# gvs1.net
KiCad netlist of a schematic drawn in EAGLE
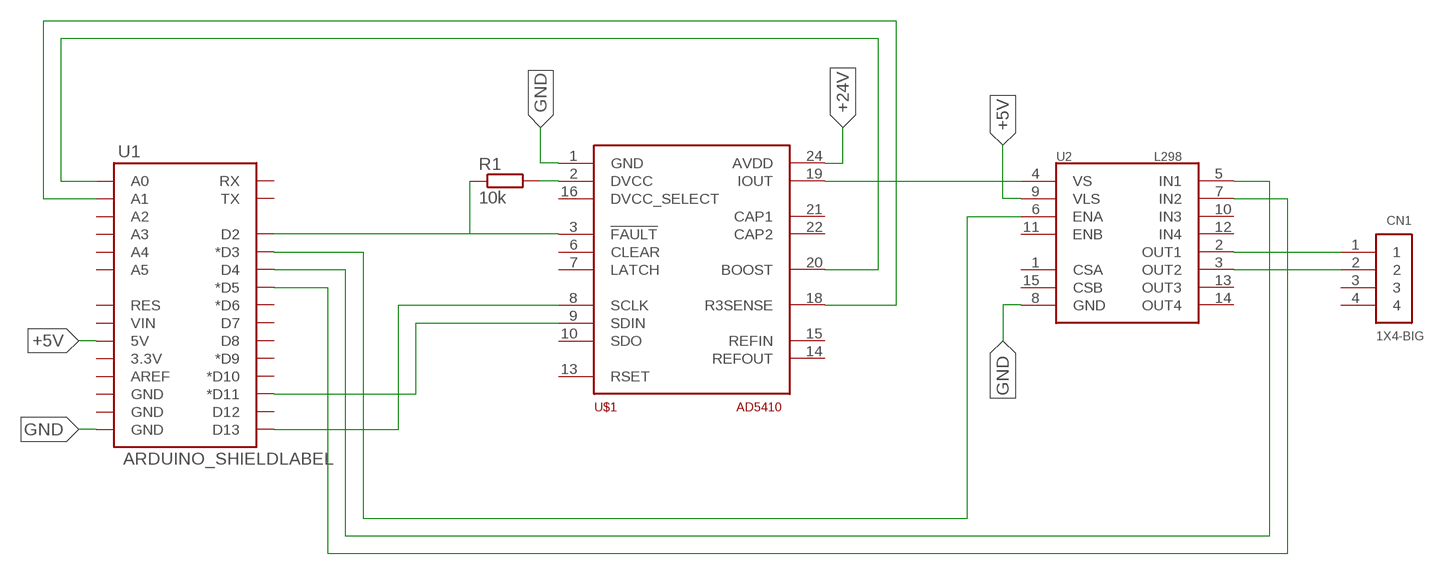
[diagram p0: schematic, sheet 1]

(export (version "E")
  (design (tool "Eeschema 10.0.6"))
  (components
    (comp (ref "CN1")
      (value "1X4-BIG")
      (footprint "eagle-import:1X04-BIG")
      (libsource (lib "eagle-import") (part "1X4-BIG"))
    )
    (comp (ref "R1")
      (value "10k")
      (footprint "eagle-import:0204V")
      (libsource (lib "eagle-import") (part "R-EU_0204/2V"))
    )
    (comp (ref "U$1")
      (value "AD5410")
      (footprint "eagle-import:TSSOP24")
      (libsource (lib "eagle-import") (part "AD5410"))
    )
    (comp (ref "U1")
      (value "ARDUINO_SHIELDLABEL")
      (footprint "eagle-import:DUEMILANOVE_SHIELD")
      (libsource (lib "eagle-import") (part "ARDUINO_SHIELDLABEL"))
    )
    (comp (ref "U2")
      (value "L298")
      (footprint "eagle-import:MULTIWATT15")
      (libsource (lib "eagle-import") (part "L298"))
    )
  )
  (nets
    (net (code "1") (name "+5V") (class "Default")
      (node (ref "U1") (pin "5V") (pinfunction "5V_5V") (pintype "bidirectional"))
      (node (ref "U2") (pin "9") (pinfunction "VLS_9") (pintype "bidirectional"))
    )
    (net (code "2") (name "+24V") (class "Default")
      (node (ref "U$1") (pin "24") (pinfunction "AVDD_24") (pintype "bidirectional"))
    )
    (net (code "3") (name "GND") (class "Default")
      (node (ref "U$1") (pin "1") (pinfunction "GND_1") (pintype "bidirectional"))
      (node (ref "U1") (pin "GND@0") (pinfunction "GND_GND@0") (pintype "bidirectional"))
      (node (ref "U2") (pin "8") (pinfunction "GND_8") (pintype "bidirectional"))
    )
    (net (code "4") (name "Net-(U$1-BOOST)") (class "Default")
      (node (ref "U$1") (pin "20") (pinfunction "BOOST_20") (pintype "bidirectional"))
      (node (ref "U1") (pin "A0") (pinfunction "A0_A0") (pintype "bidirectional"))
    )
    (net (code "5") (name "Net-(U$1-DVCC)") (class "Default")
      (node (ref "R1") (pin "2") (pinfunction "2_2") (pintype "passive"))
      (node (ref "U$1") (pin "2") (pinfunction "DVCC_2") (pintype "bidirectional"))
    )
    (net (code "6") (name "Net-(U$1-IOUT)") (class "Default")
      (node (ref "U$1") (pin "19") (pinfunction "IOUT_19") (pintype "bidirectional"))
      (node (ref "U2") (pin "4") (pinfunction "VS_4") (pintype "bidirectional"))
    )
    (net (code "7") (name "Net-(U$1-R3SENSE)") (class "Default")
      (node (ref "U$1") (pin "18") (pinfunction "R3SENSE_18") (pintype "bidirectional"))
      (node (ref "U1") (pin "A1") (pinfunction "A1_A1") (pintype "bidirectional"))
    )
    (net (code "8") (name "Net-(U$1-SCLK)") (class "Default")
      (node (ref "U$1") (pin "8") (pinfunction "SCLK_8") (pintype "bidirectional"))
      (node (ref "U1") (pin "D13") (pinfunction "D13_D13") (pintype "bidirectional"))
    )
    (net (code "9") (name "Net-(U$1-SDIN)") (class "Default")
      (node (ref "U$1") (pin "9") (pinfunction "SDIN_9") (pintype "bidirectional"))
      (node (ref "U1") (pin "D11") (pinfunction "*D11_D11") (pintype "bidirectional"))
    )
    (net (code "10") (name "Net-(U$1-~{FAULT})") (class "Default")
      (node (ref "R1") (pin "1") (pinfunction "1_1") (pintype "passive"))
      (node (ref "U$1") (pin "3") (pinfunction "~{FAULT}_3") (pintype "bidirectional"))
      (node (ref "U1") (pin "D2") (pinfunction "D2_D2") (pintype "bidirectional"))
    )
    (net (code "11") (name "Net-(U1-*D3)") (class "Default")
      (node (ref "U1") (pin "D3") (pinfunction "*D3_D3") (pintype "bidirectional"))
      (node (ref "U2") (pin "6") (pinfunction "ENA_6") (pintype "bidirectional"))
    )
    (net (code "12") (name "Net-(U1-*D5)") (class "Default")
      (node (ref "U1") (pin "D5") (pinfunction "*D5_D5") (pintype "bidirectional"))
      (node (ref "U2") (pin "7") (pinfunction "IN2_7") (pintype "bidirectional"))
    )
    (net (code "13") (name "Net-(U2-IN1)") (class "Default")
      (node (ref "U1") (pin "D4") (pinfunction "D4_D4") (pintype "bidirectional"))
      (node (ref "U2") (pin "5") (pinfunction "IN1_5") (pintype "bidirectional"))
    )
    (net (code "14") (name "Net-(U2-OUT1)") (class "Default")
      (node (ref "CN1") (pin "1") (pinfunction "1_1") (pintype "bidirectional"))
      (node (ref "U2") (pin "2") (pinfunction "OUT1_2") (pintype "bidirectional"))
    )
    (net (code "15") (name "Net-(U2-OUT2)") (class "Default")
      (node (ref "CN1") (pin "2") (pinfunction "2_2") (pintype "bidirectional"))
      (node (ref "U2") (pin "3") (pinfunction "OUT2_3") (pintype "bidirectional"))
    )
    (net (code "16") (name "unconnected-(CN1-Pad3)") (class "Default")
      (node (ref "CN1") (pin "3") (pinfunction "3_3") (pintype "bidirectional"))
    )
    (net (code "17") (name "unconnected-(CN1-Pad4)") (class "Default")
      (node (ref "CN1") (pin "4") (pinfunction "4_4") (pintype "bidirectional"))
    )
    (net (code "18") (name "unconnected-(U$1-CAP1-Pad21)") (class "Default")
      (node (ref "U$1") (pin "21") (pinfunction "CAP1_21") (pintype "bidirectional"))
    )
    (net (code "19") (name "unconnected-(U$1-CAP2-Pad22)") (class "Default")
      (node (ref "U$1") (pin "22") (pinfunction "CAP2_22") (pintype "bidirectional"))
    )
    (net (code "20") (name "unconnected-(U$1-CLEAR-Pad6)") (class "Default")
      (node (ref "U$1") (pin "6") (pinfunction "CLEAR_6") (pintype "bidirectional"))
    )
    (net (code "21") (name "unconnected-(U$1-DVCC_SELECT-Pad16)") (class "Default")
      (node (ref "U$1") (pin "16") (pinfunction "DVCC_SELECT_16") (pintype "bidirectional"))
    )
    (net (code "22") (name "unconnected-(U$1-LATCH-Pad7)") (class "Default")
      (node (ref "U$1") (pin "7") (pinfunction "LATCH_7") (pintype "bidirectional"))
    )
    (net (code "23") (name "unconnected-(U$1-REFIN-Pad15)") (class "Default")
      (node (ref "U$1") (pin "15") (pinfunction "REFIN_15") (pintype "bidirectional"))
    )
    (net (code "24") (name "unconnected-(U$1-REFOUT-Pad14)") (class "Default")
      (node (ref "U$1") (pin "14") (pinfunction "REFOUT_14") (pintype "bidirectional"))
    )
    (net (code "25") (name "unconnected-(U$1-RSET-Pad13)") (class "Default")
      (node (ref "U$1") (pin "13") (pinfunction "RSET_13") (pintype "bidirectional"))
    )
    (net (code "26") (name "unconnected-(U$1-SDO-Pad10)") (class "Default")
      (node (ref "U$1") (pin "10") (pinfunction "SDO_10") (pintype "bidirectional"))
    )
    (net (code "27") (name "unconnected-(U1-*D6-PadD6)") (class "Default")
      (node (ref "U1") (pin "D6") (pinfunction "*D6_D6") (pintype "bidirectional"))
    )
    (net (code "28") (name "unconnected-(U1-*D9-PadD9)") (class "Default")
      (node (ref "U1") (pin "D9") (pinfunction "*D9_D9") (pintype "bidirectional"))
    )
    (net (code "29") (name "unconnected-(U1-*D10-PadD10)") (class "Default")
      (node (ref "U1") (pin "D10") (pinfunction "*D10_D10") (pintype "bidirectional"))
    )
    (net (code "30") (name "unconnected-(U1-GND-PadGND@1)") (class "Default")
      (node (ref "U1") (pin "GND@1") (pinfunction "GND_GND@1") (pintype "bidirectional"))
    )
    (net (code "31") (name "unconnected-(U1-GND-PadGND@2)") (class "Default")
      (node (ref "U1") (pin "GND@2") (pinfunction "GND_GND@2") (pintype "bidirectional"))
    )
    (net (code "32") (name "unconnected-(U1-Pad3.3V)") (class "Default")
      (node (ref "U1") (pin "3.3V") (pinfunction "3.3V_3.3V") (pintype "bidirectional"))
    )
    (net (code "33") (name "unconnected-(U1-PadA2)") (class "Default")
      (node (ref "U1") (pin "A2") (pinfunction "A2_A2") (pintype "bidirectional"))
    )
    (net (code "34") (name "unconnected-(U1-PadA3)") (class "Default")
      (node (ref "U1") (pin "A3") (pinfunction "A3_A3") (pintype "bidirectional"))
    )
    (net (code "35") (name "unconnected-(U1-PadA4)") (class "Default")
      (node (ref "U1") (pin "A4") (pinfunction "A4_A4") (pintype "bidirectional"))
    )
    (net (code "36") (name "unconnected-(U1-PadA5)") (class "Default")
      (node (ref "U1") (pin "A5") (pinfunction "A5_A5") (pintype "bidirectional"))
    )
    (net (code "37") (name "unconnected-(U1-PadAREF)") (class "Default")
      (node (ref "U1") (pin "AREF") (pinfunction "AREF_AREF") (pintype "bidirectional"))
    )
    (net (code "38") (name "unconnected-(U1-PadD7)") (class "Default")
      (node (ref "U1") (pin "D7") (pinfunction "D7_D7") (pintype "bidirectional"))
    )
    (net (code "39") (name "unconnected-(U1-PadD8)") (class "Default")
      (node (ref "U1") (pin "D8") (pinfunction "D8_D8") (pintype "bidirectional"))
    )
    (net (code "40") (name "unconnected-(U1-PadD12)") (class "Default")
      (node (ref "U1") (pin "D12") (pinfunction "D12_D12") (pintype "bidirectional"))
    )
    (net (code "41") (name "unconnected-(U1-PadRES)") (class "Default")
      (node (ref "U1") (pin "RES") (pinfunction "RES_RES") (pintype "bidirectional"))
    )
    (net (code "42") (name "unconnected-(U1-PadRX)") (class "Default")
      (node (ref "U1") (pin "RX") (pinfunction "RX_RX") (pintype "bidirectional"))
    )
    (net (code "43") (name "unconnected-(U1-PadTX)") (class "Default")
      (node (ref "U1") (pin "TX") (pinfunction "TX_TX") (pintype "bidirectional"))
    )
    (net (code "44") (name "unconnected-(U1-PadVIN)") (class "Default")
      (node (ref "U1") (pin "VIN") (pinfunction "VIN_VIN") (pintype "bidirectional"))
    )
    (net (code "45") (name "unconnected-(U2-CSA-Pad1)") (class "Default")
      (node (ref "U2") (pin "1") (pinfunction "CSA_1") (pintype "bidirectional"))
    )
    (net (code "46") (name "unconnected-(U2-CSB-Pad15)") (class "Default")
      (node (ref "U2") (pin "15") (pinfunction "CSB_15") (pintype "bidirectional"))
    )
    (net (code "47") (name "unconnected-(U2-ENB-Pad11)") (class "Default")
      (node (ref "U2") (pin "11") (pinfunction "ENB_11") (pintype "bidirectional"))
    )
    (net (code "48") (name "unconnected-(U2-IN3-Pad10)") (class "Default")
      (node (ref "U2") (pin "10") (pinfunction "IN3_10") (pintype "bidirectional"))
    )
    (net (code "49") (name "unconnected-(U2-IN4-Pad12)") (class "Default")
      (node (ref "U2") (pin "12") (pinfunction "IN4_12") (pintype "bidirectional"))
    )
    (net (code "50") (name "unconnected-(U2-OUT3-Pad13)") (class "Default")
      (node (ref "U2") (pin "13") (pinfunction "OUT3_13") (pintype "bidirectional"))
    )
    (net (code "51") (name "unconnected-(U2-OUT4-Pad14)") (class "Default")
      (node (ref "U2") (pin "14") (pinfunction "OUT4_14") (pintype "bidirectional"))
    )
  )
)
